# SCH_RPdrums_2024-07-31.net
KiCad netlist of a schematic drawn in EasyEDA
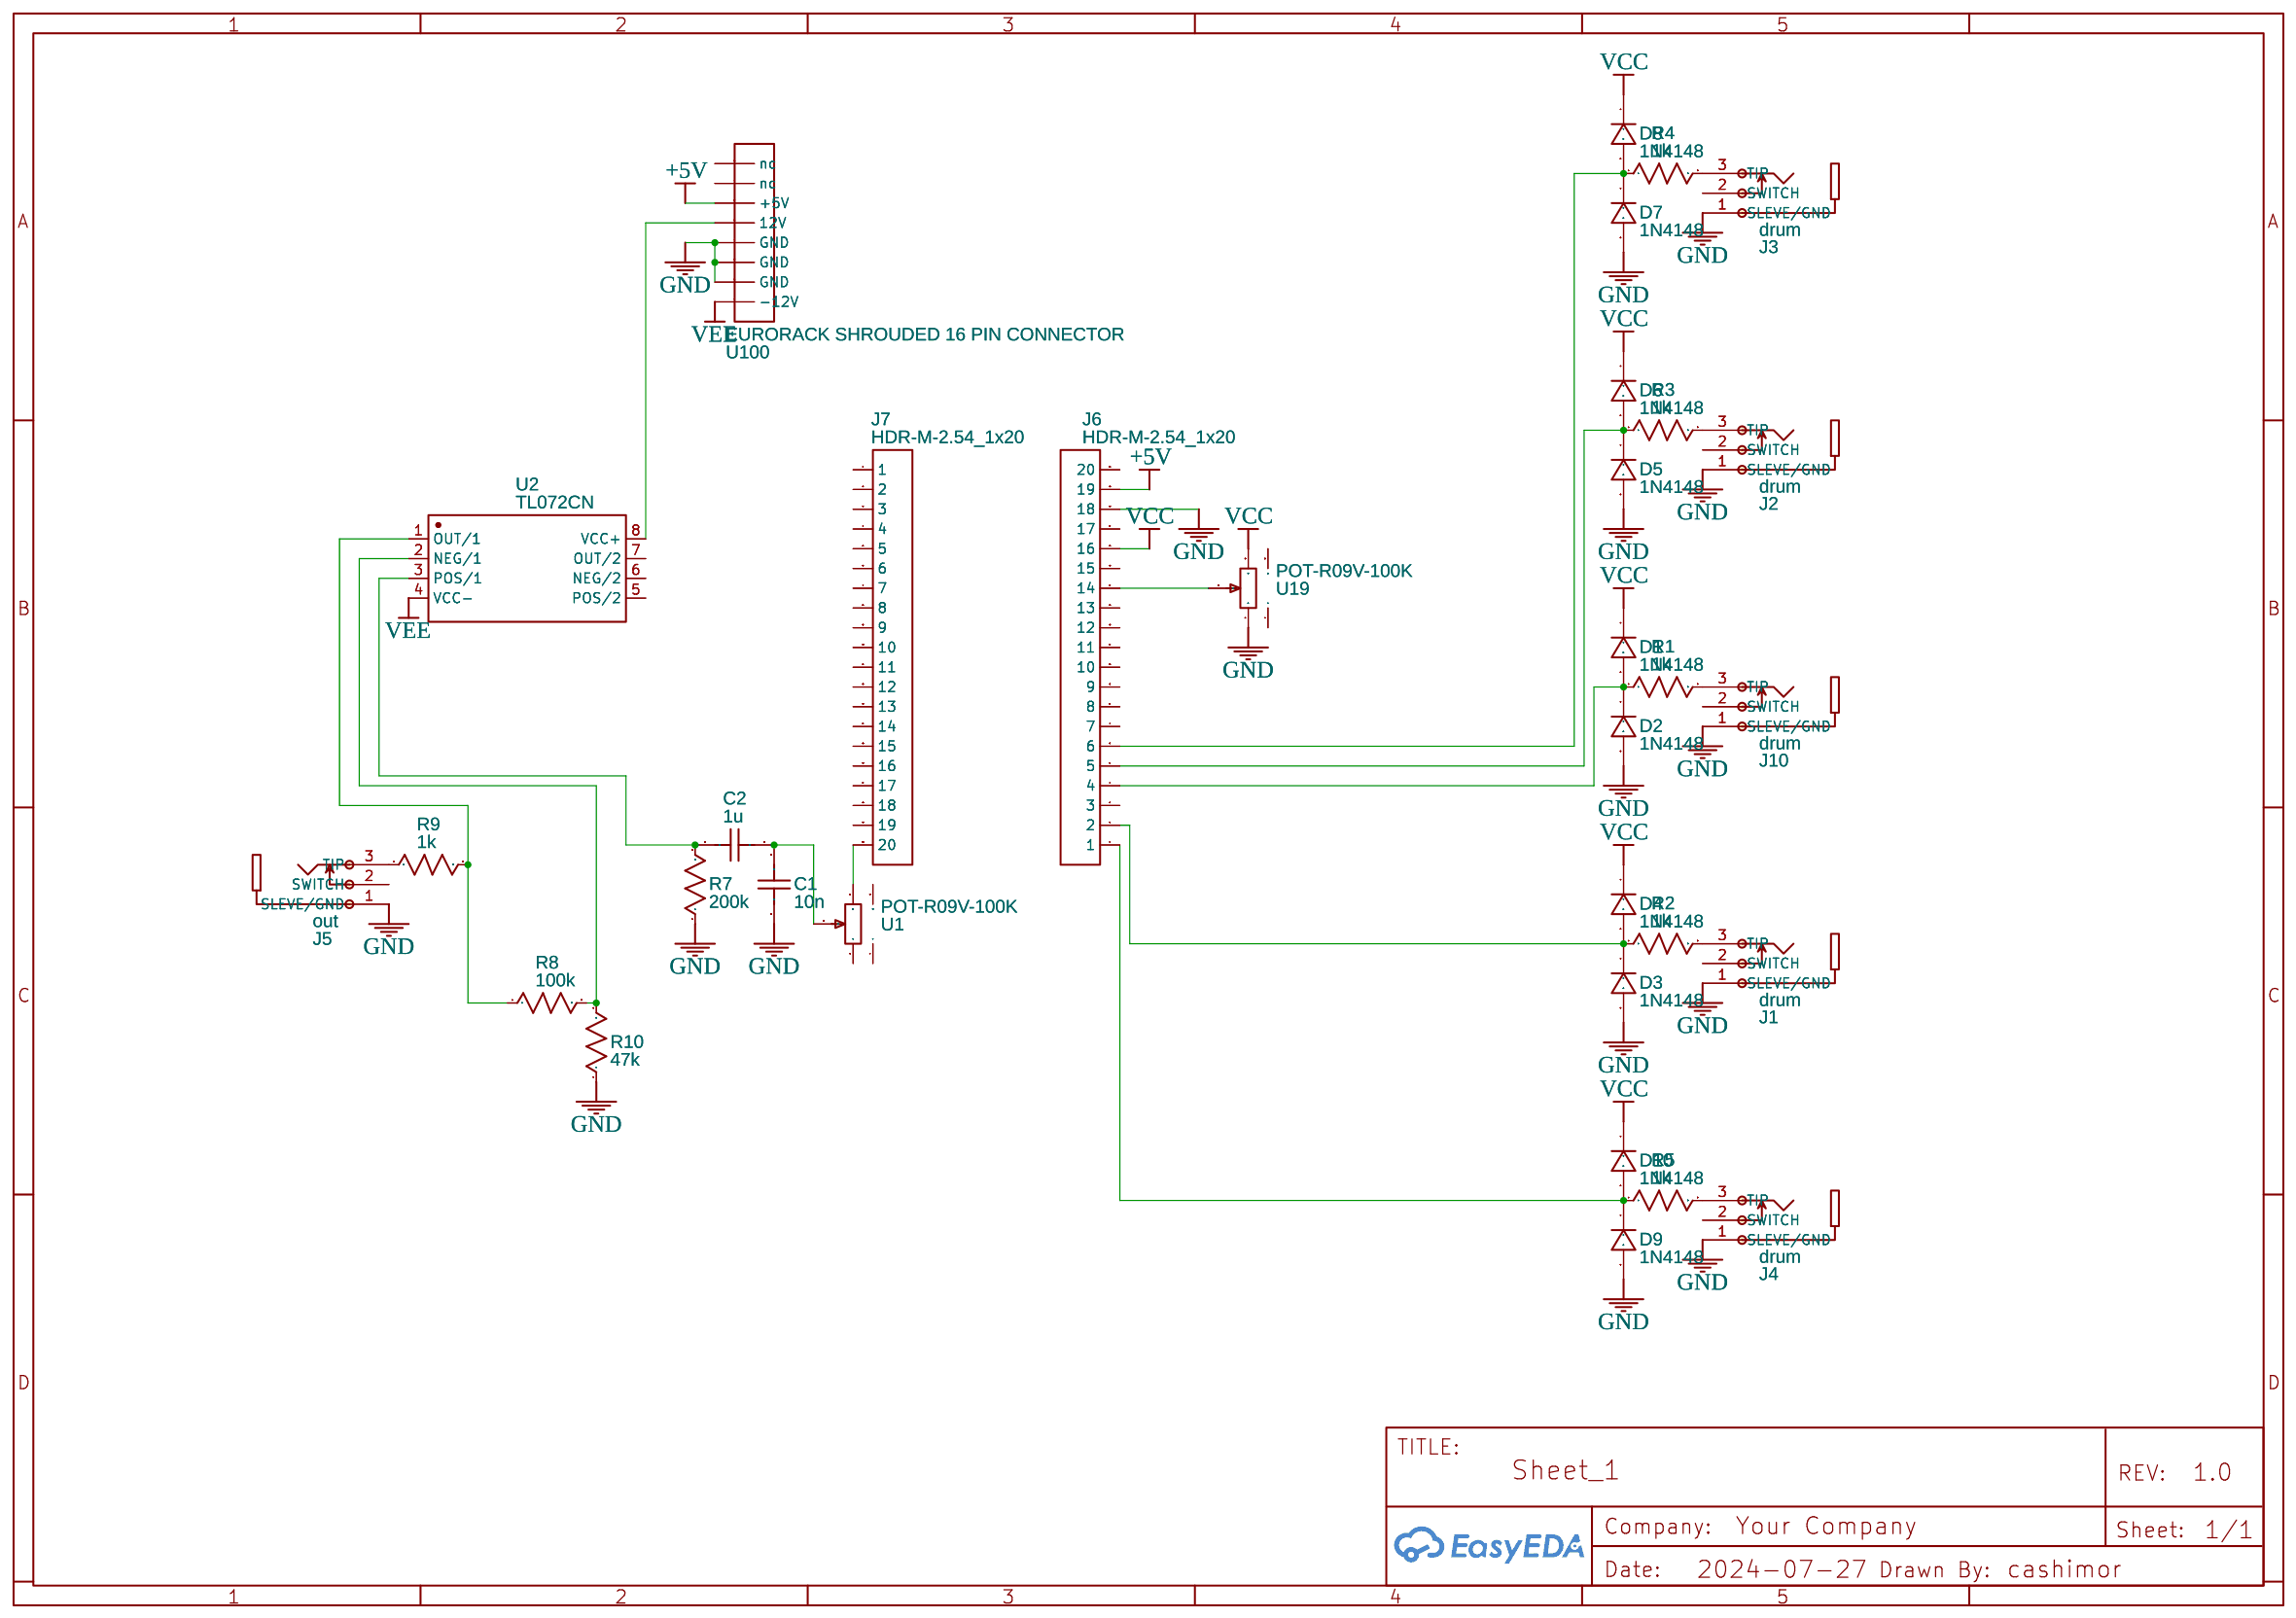
[diagram p0: schematic sheet]

(export (version "E")
  (design (tool "Eeschema 10.0.6"))
  (components
    (comp (ref "C1") (value "10n") (libsource (lib "") (part "C_RAD-0.1_US")))
    (comp (ref "C2") (value "1u") (libsource (lib "") (part "C_RAD-0.1_US_1")))
    (comp (ref "D1")
      (value "1N4148")
      (fields (field (name "Manufacturer") "STMicroelectronics"))
      (libsource (lib "") (part "1N4148"))
    )
    (comp (ref "D2")
      (value "1N4148")
      (fields (field (name "Manufacturer") "STMicroelectronics"))
      (libsource (lib "") (part "1N4148"))
    )
    (comp (ref "D3")
      (value "1N4148")
      (fields (field (name "Manufacturer") "STMicroelectronics"))
      (libsource (lib "") (part "1N4148"))
    )
    (comp (ref "D4")
      (value "1N4148")
      (fields (field (name "Manufacturer") "STMicroelectronics"))
      (libsource (lib "") (part "1N4148"))
    )
    (comp (ref "D5")
      (value "1N4148")
      (fields (field (name "Manufacturer") "STMicroelectronics"))
      (libsource (lib "") (part "1N4148"))
    )
    (comp (ref "D6")
      (value "1N4148")
      (fields (field (name "Manufacturer") "STMicroelectronics"))
      (libsource (lib "") (part "1N4148"))
    )
    (comp (ref "D7")
      (value "1N4148")
      (fields (field (name "Manufacturer") "STMicroelectronics"))
      (libsource (lib "") (part "1N4148"))
    )
    (comp (ref "D8")
      (value "1N4148")
      (fields (field (name "Manufacturer") "STMicroelectronics"))
      (libsource (lib "") (part "1N4148"))
    )
    (comp (ref "D9")
      (value "1N4148")
      (fields (field (name "Manufacturer") "STMicroelectronics"))
      (libsource (lib "") (part "1N4148"))
    )
    (comp (ref "D10")
      (value "1N4148")
      (fields (field (name "Manufacturer") "STMicroelectronics"))
      (libsource (lib "") (part "1N4148"))
    )
    (comp (ref "J1")
      (value "drum")
      (fields (field (name "Manufacturer Part") "Thonk"))
      (libsource (lib "") (part "THONKICONN_1_1"))
    )
    (comp (ref "J2")
      (value "drum")
      (fields (field (name "Manufacturer Part") "Thonk"))
      (libsource (lib "") (part "THONKICONN_1_1"))
    )
    (comp (ref "J3")
      (value "drum")
      (fields (field (name "Manufacturer Part") "Thonk"))
      (libsource (lib "") (part "THONKICONN_1_1"))
    )
    (comp (ref "J4")
      (value "drum")
      (fields (field (name "Manufacturer Part") "Thonk"))
      (libsource (lib "") (part "THONKICONN_1_1"))
    )
    (comp (ref "J5")
      (value "out")
      (fields (field (name "Manufacturer Part") "Thonk"))
      (libsource (lib "") (part "THONKICONN_1"))
    )
    (comp (ref "J6") (value "HDR-M-2.54_1x20") (libsource (lib "") (part "HDR-M-2.54_1x20_1")))
    (comp (ref "J7") (value "HDR-M-2.54_1x20") (libsource (lib "") (part "HDR-M-2.54_1x20")))
    (comp (ref "J10")
      (value "drum")
      (fields (field (name "Manufacturer Part") "Thonk"))
      (libsource (lib "") (part "THONKICONN_1_1"))
    )
    (comp (ref "R1") (value "1k") (libsource (lib "") (part "R_AXIAL-0.3_US")))
    (comp (ref "R2") (value "1k") (libsource (lib "") (part "R_AXIAL-0.3_US")))
    (comp (ref "R3") (value "1k") (libsource (lib "") (part "R_AXIAL-0.3_US")))
    (comp (ref "R4") (value "1k") (libsource (lib "") (part "R_AXIAL-0.3_US")))
    (comp (ref "R5") (value "1k") (libsource (lib "") (part "R_AXIAL-0.3_US")))
    (comp (ref "R7") (value "200k") (libsource (lib "") (part "R_AXIAL-0.3_US_1")))
    (comp (ref "R8") (value "100k") (libsource (lib "") (part "R_AXIAL-0.3_US")))
    (comp (ref "R9") (value "1k") (libsource (lib "") (part "R_AXIAL-0.3_US")))
    (comp (ref "R10") (value "47k") (libsource (lib "") (part "R_AXIAL-0.3_US_1")))
    (comp (ref "U1") (value "POT-R09V-100K") (libsource (lib "") (part "POT-R09V-100K")))
    (comp (ref "U2")
      (value "TL072CN")
      (fields (field (name "Manufacturer") "STMicroelectronics"))
      (libsource (lib "") (part "TL072CN"))
    )
    (comp (ref "U19") (value "POT-R09V-100K") (libsource (lib "") (part "POT-R09V-100K")))
    (comp (ref "U100")
      (value "EURORACK SHROUDED 16 PIN CONNECTOR")
      (fields (field (name "Manufacturer Part") "New SchematicLib"))
      (libsource (lib "") (part "EURORACK SHROUDED 16 PIN CONNECTOR"))
    )
  )
  (nets
    (net (code "1") (name "+5V") (class "Default")
      (node (ref "J6") (pin "19") (pinfunction "19_19") (pintype "unspecified"))
      (node (ref "U100") (pin "6") (pinfunction "+5V_6") (pintype "unspecified"))
    )
    (net (code "2") (name "GND") (class "Default")
      (node (ref "C1") (pin "1") (pinfunction "1_1") (pintype "unspecified"))
      (node (ref "D2") (pin "2") (pinfunction "2_2") (pintype "unspecified"))
      (node (ref "D3") (pin "2") (pinfunction "2_2") (pintype "unspecified"))
      (node (ref "D5") (pin "2") (pinfunction "2_2") (pintype "unspecified"))
      (node (ref "D7") (pin "2") (pinfunction "2_2") (pintype "unspecified"))
      (node (ref "D9") (pin "2") (pinfunction "2_2") (pintype "unspecified"))
      (node (ref "J1") (pin "1") (pinfunction "SLEVE/GND_1") (pintype "unspecified"))
      (node (ref "J10") (pin "1") (pinfunction "SLEVE/GND_1") (pintype "unspecified"))
      (node (ref "J2") (pin "1") (pinfunction "SLEVE/GND_1") (pintype "unspecified"))
      (node (ref "J3") (pin "1") (pinfunction "SLEVE/GND_1") (pintype "unspecified"))
      (node (ref "J4") (pin "1") (pinfunction "SLEVE/GND_1") (pintype "unspecified"))
      (node (ref "J5") (pin "1") (pinfunction "SLEVE/GND_1") (pintype "unspecified"))
      (node (ref "J6") (pin "18") (pinfunction "18_18") (pintype "unspecified"))
      (node (ref "R10") (pin "1") (pinfunction "1_1") (pintype "unspecified"))
      (node (ref "R7") (pin "1") (pinfunction "1_1") (pintype "unspecified"))
      (node (ref "U100") (pin "2") (pinfunction "GND_2") (pintype "unspecified"))
      (node (ref "U100") (pin "3") (pinfunction "GND_3") (pintype "unspecified"))
      (node (ref "U100") (pin "4") (pinfunction "GND_4") (pintype "unspecified"))
      (node (ref "U19") (pin "1") (pinfunction "1_1") (pintype "input"))
    )
    (net (code "3") (name "Net-(C1-Pad2)") (class "Default")
      (node (ref "C1") (pin "2") (pinfunction "2_2") (pintype "unspecified"))
      (node (ref "C2") (pin "2") (pinfunction "2_2") (pintype "unspecified"))
      (node (ref "U1") (pin "2") (pinfunction "2_2") (pintype "input"))
    )
    (net (code "4") (name "Net-(D1-Pad2)") (class "Default")
      (node (ref "D1") (pin "2") (pinfunction "2_2") (pintype "unspecified"))
      (node (ref "D2") (pin "1") (pinfunction "1_1") (pintype "unspecified"))
      (node (ref "J6") (pin "4") (pinfunction "4_4") (pintype "unspecified"))
      (node (ref "R1") (pin "1") (pinfunction "1_1") (pintype "unspecified"))
    )
    (net (code "5") (name "Net-(D3-Pad1)") (class "Default")
      (node (ref "D3") (pin "1") (pinfunction "1_1") (pintype "unspecified"))
      (node (ref "D4") (pin "2") (pinfunction "2_2") (pintype "unspecified"))
      (node (ref "J6") (pin "2") (pinfunction "2_2") (pintype "unspecified"))
      (node (ref "R2") (pin "1") (pinfunction "1_1") (pintype "unspecified"))
    )
    (net (code "6") (name "Net-(D5-Pad1)") (class "Default")
      (node (ref "D5") (pin "1") (pinfunction "1_1") (pintype "unspecified"))
      (node (ref "D6") (pin "2") (pinfunction "2_2") (pintype "unspecified"))
      (node (ref "J6") (pin "5") (pinfunction "5_5") (pintype "unspecified"))
      (node (ref "R3") (pin "1") (pinfunction "1_1") (pintype "unspecified"))
    )
    (net (code "7") (name "Net-(D7-Pad1)") (class "Default")
      (node (ref "D7") (pin "1") (pinfunction "1_1") (pintype "unspecified"))
      (node (ref "D8") (pin "2") (pinfunction "2_2") (pintype "unspecified"))
      (node (ref "J6") (pin "6") (pinfunction "6_6") (pintype "unspecified"))
      (node (ref "R4") (pin "1") (pinfunction "1_1") (pintype "unspecified"))
    )
    (net (code "8") (name "Net-(D10-Pad2)") (class "Default")
      (node (ref "D10") (pin "2") (pinfunction "2_2") (pintype "unspecified"))
      (node (ref "D9") (pin "1") (pinfunction "1_1") (pintype "unspecified"))
      (node (ref "J6") (pin "1") (pinfunction "1_1") (pintype "unspecified"))
      (node (ref "R5") (pin "1") (pinfunction "1_1") (pintype "unspecified"))
    )
    (net (code "9") (name "Net-(J1-TIP)") (class "Default")
      (node (ref "J1") (pin "3") (pinfunction "TIP_3") (pintype "unspecified"))
      (node (ref "R2") (pin "2") (pinfunction "2_2") (pintype "unspecified"))
    )
    (net (code "10") (name "Net-(J2-TIP)") (class "Default")
      (node (ref "J2") (pin "3") (pinfunction "TIP_3") (pintype "unspecified"))
      (node (ref "R3") (pin "2") (pinfunction "2_2") (pintype "unspecified"))
    )
    (net (code "11") (name "Net-(J3-TIP)") (class "Default")
      (node (ref "J3") (pin "3") (pinfunction "TIP_3") (pintype "unspecified"))
      (node (ref "R4") (pin "2") (pinfunction "2_2") (pintype "unspecified"))
    )
    (net (code "12") (name "Net-(J4-TIP)") (class "Default")
      (node (ref "J4") (pin "3") (pinfunction "TIP_3") (pintype "unspecified"))
      (node (ref "R5") (pin "2") (pinfunction "2_2") (pintype "unspecified"))
    )
    (net (code "13") (name "Net-(J5-TIP)") (class "Default")
      (node (ref "J5") (pin "3") (pinfunction "TIP_3") (pintype "unspecified"))
      (node (ref "R9") (pin "1") (pinfunction "1_1") (pintype "unspecified"))
    )
    (net (code "14") (name "Net-(J6-Pad14)") (class "Default")
      (node (ref "J6") (pin "14") (pinfunction "14_14") (pintype "unspecified"))
      (node (ref "U19") (pin "2") (pinfunction "2_2") (pintype "input"))
    )
    (net (code "15") (name "Net-(J7-Pad20)") (class "Default")
      (node (ref "J7") (pin "20") (pinfunction "20_20") (pintype "unspecified"))
      (node (ref "U1") (pin "3") (pinfunction "3_3") (pintype "input"))
    )
    (net (code "16") (name "Net-(J10-TIP)") (class "Default")
      (node (ref "J10") (pin "3") (pinfunction "TIP_3") (pintype "unspecified"))
      (node (ref "R1") (pin "2") (pinfunction "2_2") (pintype "unspecified"))
    )
    (net (code "17") (name "Net-(U2-NEG{slash}1)") (class "Default")
      (node (ref "R10") (pin "2") (pinfunction "2_2") (pintype "unspecified"))
      (node (ref "R8") (pin "2") (pinfunction "2_2") (pintype "unspecified"))
      (node (ref "U2") (pin "2") (pinfunction "NEG/1_2") (pintype "unspecified"))
    )
    (net (code "18") (name "Net-(U2-OUT{slash}1)") (class "Default")
      (node (ref "R8") (pin "1") (pinfunction "1_1") (pintype "unspecified"))
      (node (ref "R9") (pin "2") (pinfunction "2_2") (pintype "unspecified"))
      (node (ref "U2") (pin "1") (pinfunction "OUT/1_1") (pintype "unspecified"))
    )
    (net (code "19") (name "Net-(U2-POS{slash}1)") (class "Default")
      (node (ref "C2") (pin "1") (pinfunction "1_1") (pintype "unspecified"))
      (node (ref "R7") (pin "2") (pinfunction "2_2") (pintype "unspecified"))
      (node (ref "U2") (pin "3") (pinfunction "POS/1_3") (pintype "unspecified"))
    )
    (net (code "20") (name "Net-(U100-12V)") (class "Default")
      (node (ref "U100") (pin "5") (pinfunction "12V_5") (pintype "unspecified"))
      (node (ref "U2") (pin "8") (pinfunction "VCC+_8") (pintype "unspecified"))
    )
    (net (code "21") (name "VCC") (class "Default")
      (node (ref "D1") (pin "1") (pinfunction "1_1") (pintype "unspecified"))
      (node (ref "D10") (pin "1") (pinfunction "1_1") (pintype "unspecified"))
      (node (ref "D4") (pin "1") (pinfunction "1_1") (pintype "unspecified"))
      (node (ref "D6") (pin "1") (pinfunction "1_1") (pintype "unspecified"))
      (node (ref "D8") (pin "1") (pinfunction "1_1") (pintype "unspecified"))
      (node (ref "J6") (pin "16") (pinfunction "16_16") (pintype "unspecified"))
      (node (ref "U19") (pin "3") (pinfunction "3_3") (pintype "input"))
    )
    (net (code "22") (name "VEE") (class "Default")
      (node (ref "U100") (pin "1") (pinfunction "-12V_1") (pintype "unspecified"))
      (node (ref "U2") (pin "4") (pinfunction "VCC-_4") (pintype "unspecified"))
    )
    (net (code "23") (name "unconnected-(J1-SWITCH-Pad2)") (class "Default")
      (node (ref "J1") (pin "2") (pinfunction "SWITCH_2") (pintype "unspecified"))
    )
    (net (code "24") (name "unconnected-(J2-SWITCH-Pad2)") (class "Default")
      (node (ref "J2") (pin "2") (pinfunction "SWITCH_2") (pintype "unspecified"))
    )
    (net (code "25") (name "unconnected-(J3-SWITCH-Pad2)") (class "Default")
      (node (ref "J3") (pin "2") (pinfunction "SWITCH_2") (pintype "unspecified"))
    )
    (net (code "26") (name "unconnected-(J4-SWITCH-Pad2)") (class "Default")
      (node (ref "J4") (pin "2") (pinfunction "SWITCH_2") (pintype "unspecified"))
    )
    (net (code "27") (name "unconnected-(J5-SWITCH-Pad2)") (class "Default")
      (node (ref "J5") (pin "2") (pinfunction "SWITCH_2") (pintype "unspecified"))
    )
    (net (code "28") (name "unconnected-(J6-Pad3)") (class "Default")
      (node (ref "J6") (pin "3") (pinfunction "3_3") (pintype "unspecified"))
    )
    (net (code "29") (name "unconnected-(J6-Pad7)") (class "Default")
      (node (ref "J6") (pin "7") (pinfunction "7_7") (pintype "unspecified"))
    )
    (net (code "30") (name "unconnected-(J6-Pad8)") (class "Default")
      (node (ref "J6") (pin "8") (pinfunction "8_8") (pintype "unspecified"))
    )
    (net (code "31") (name "unconnected-(J6-Pad9)") (class "Default")
      (node (ref "J6") (pin "9") (pinfunction "9_9") (pintype "unspecified"))
    )
    (net (code "32") (name "unconnected-(J6-Pad10)") (class "Default")
      (node (ref "J6") (pin "10") (pinfunction "10_10") (pintype "unspecified"))
    )
    (net (code "33") (name "unconnected-(J6-Pad11)") (class "Default")
      (node (ref "J6") (pin "11") (pinfunction "11_11") (pintype "unspecified"))
    )
    (net (code "34") (name "unconnected-(J6-Pad12)") (class "Default")
      (node (ref "J6") (pin "12") (pinfunction "12_12") (pintype "unspecified"))
    )
    (net (code "35") (name "unconnected-(J6-Pad13)") (class "Default")
      (node (ref "J6") (pin "13") (pinfunction "13_13") (pintype "unspecified"))
    )
    (net (code "36") (name "unconnected-(J6-Pad15)") (class "Default")
      (node (ref "J6") (pin "15") (pinfunction "15_15") (pintype "unspecified"))
    )
    (net (code "37") (name "unconnected-(J6-Pad17)") (class "Default")
      (node (ref "J6") (pin "17") (pinfunction "17_17") (pintype "unspecified"))
    )
    (net (code "38") (name "unconnected-(J6-Pad20)") (class "Default")
      (node (ref "J6") (pin "20") (pinfunction "20_20") (pintype "unspecified"))
    )
    (net (code "39") (name "unconnected-(J7-Pad1)") (class "Default")
      (node (ref "J7") (pin "1") (pinfunction "1_1") (pintype "unspecified"))
    )
    (net (code "40") (name "unconnected-(J7-Pad2)") (class "Default")
      (node (ref "J7") (pin "2") (pinfunction "2_2") (pintype "unspecified"))
    )
    (net (code "41") (name "unconnected-(J7-Pad3)") (class "Default")
      (node (ref "J7") (pin "3") (pinfunction "3_3") (pintype "unspecified"))
    )
    (net (code "42") (name "unconnected-(J7-Pad4)") (class "Default")
      (node (ref "J7") (pin "4") (pinfunction "4_4") (pintype "unspecified"))
    )
    (net (code "43") (name "unconnected-(J7-Pad5)") (class "Default")
      (node (ref "J7") (pin "5") (pinfunction "5_5") (pintype "unspecified"))
    )
    (net (code "44") (name "unconnected-(J7-Pad6)") (class "Default")
      (node (ref "J7") (pin "6") (pinfunction "6_6") (pintype "unspecified"))
    )
    (net (code "45") (name "unconnected-(J7-Pad7)") (class "Default")
      (node (ref "J7") (pin "7") (pinfunction "7_7") (pintype "unspecified"))
    )
    (net (code "46") (name "unconnected-(J7-Pad8)") (class "Default")
      (node (ref "J7") (pin "8") (pinfunction "8_8") (pintype "unspecified"))
    )
    (net (code "47") (name "unconnected-(J7-Pad9)") (class "Default")
      (node (ref "J7") (pin "9") (pinfunction "9_9") (pintype "unspecified"))
    )
    (net (code "48") (name "unconnected-(J7-Pad10)") (class "Default")
      (node (ref "J7") (pin "10") (pinfunction "10_10") (pintype "unspecified"))
    )
    (net (code "49") (name "unconnected-(J7-Pad11)") (class "Default")
      (node (ref "J7") (pin "11") (pinfunction "11_11") (pintype "unspecified"))
    )
    (net (code "50") (name "unconnected-(J7-Pad12)") (class "Default")
      (node (ref "J7") (pin "12") (pinfunction "12_12") (pintype "unspecified"))
    )
    (net (code "51") (name "unconnected-(J7-Pad13)") (class "Default")
      (node (ref "J7") (pin "13") (pinfunction "13_13") (pintype "unspecified"))
    )
    (net (code "52") (name "unconnected-(J7-Pad14)") (class "Default")
      (node (ref "J7") (pin "14") (pinfunction "14_14") (pintype "unspecified"))
    )
    (net (code "53") (name "unconnected-(J7-Pad15)") (class "Default")
      (node (ref "J7") (pin "15") (pinfunction "15_15") (pintype "unspecified"))
    )
    (net (code "54") (name "unconnected-(J7-Pad16)") (class "Default")
      (node (ref "J7") (pin "16") (pinfunction "16_16") (pintype "unspecified"))
    )
    (net (code "55") (name "unconnected-(J7-Pad17)") (class "Default")
      (node (ref "J7") (pin "17") (pinfunction "17_17") (pintype "unspecified"))
    )
    (net (code "56") (name "unconnected-(J7-Pad18)") (class "Default")
      (node (ref "J7") (pin "18") (pinfunction "18_18") (pintype "unspecified"))
    )
    (net (code "57") (name "unconnected-(J7-Pad19)") (class "Default")
      (node (ref "J7") (pin "19") (pinfunction "19_19") (pintype "unspecified"))
    )
    (net (code "58") (name "unconnected-(J10-SWITCH-Pad2)") (class "Default")
      (node (ref "J10") (pin "2") (pinfunction "SWITCH_2") (pintype "unspecified"))
    )
    (net (code "59") (name "unconnected-(U1-Pad1)") (class "Default")
      (node (ref "U1") (pin "1") (pinfunction "1_1") (pintype "input"))
    )
    (net (code "60") (name "unconnected-(U1-Pad4)") (class "Default")
      (node (ref "U1") (pin "4") (pinfunction "4_4") (pintype "input"))
    )
    (net (code "61") (name "unconnected-(U1-Pad5)") (class "Default")
      (node (ref "U1") (pin "5") (pinfunction "5_5") (pintype "input"))
    )
    (net (code "62") (name "unconnected-(U2-NEG{slash}2-Pad6)") (class "Default")
      (node (ref "U2") (pin "6") (pinfunction "NEG/2_6") (pintype "unspecified"))
    )
    (net (code "63") (name "unconnected-(U2-OUT{slash}2-Pad7)") (class "Default")
      (node (ref "U2") (pin "7") (pinfunction "OUT/2_7") (pintype "unspecified"))
    )
    (net (code "64") (name "unconnected-(U2-POS{slash}2-Pad5)") (class "Default")
      (node (ref "U2") (pin "5") (pinfunction "POS/2_5") (pintype "unspecified"))
    )
    (net (code "65") (name "unconnected-(U19-Pad4)") (class "Default")
      (node (ref "U19") (pin "4") (pinfunction "4_4") (pintype "input"))
    )
    (net (code "66") (name "unconnected-(U19-Pad5)") (class "Default")
      (node (ref "U19") (pin "5") (pinfunction "5_5") (pintype "input"))
    )
    (net (code "67") (name "unconnected-(U100-nc-Pad7)") (class "Default")
      (node (ref "U100") (pin "7") (pinfunction "nc_7") (pintype "unspecified"))
    )
    (net (code "68") (name "unconnected-(U100-nc-Pad8)") (class "Default")
      (node (ref "U100") (pin "8") (pinfunction "nc_8") (pintype "unspecified"))
    )
  )
)
